# routed.net
KiCad netlist of a schematic drawn in Altium Designer
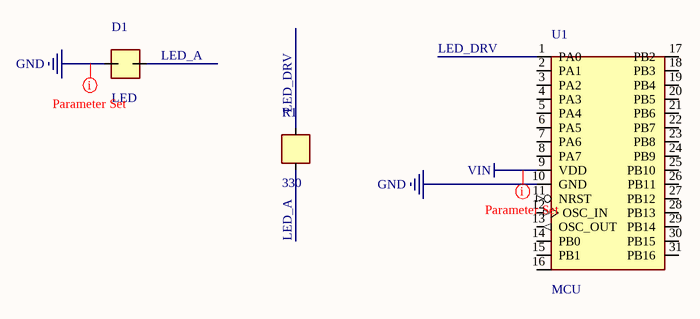
[diagram p0: routed.SchDoc]

(export (version "E")
  (design (tool "Eeschema 10.0.6"))
  (components
    (comp (ref "D1")
      (value "LED")
      (footprint "routed:Mini_LED_THT_3mm")
      (libsource (lib "routed") (part "Mini_LED"))
    )
    (comp (ref "R1")
      (value "330")
      (footprint "routed:Mini_R_0603")
      (libsource (lib "routed") (part "Mini_R"))
    )
    (comp (ref "U1")
      (value "MCU")
      (footprint "routed:Mini_QFP-32_7x7mm_P0.8mm")
      (libsource (lib "routed") (part "Mini_QFP32_IC"))
    )
  )
  (nets
    (net (code "1") (name "/LED_A") (class "Default")
      (node (ref "D1") (pin "2") (pinfunction "A_2") (pintype "passive"))
      (node (ref "R1") (pin "2") (pintype "passive"))
    )
    (net (code "2") (name "/LED_DRV") (class "Default")
      (node (ref "R1") (pin "1") (pintype "passive"))
      (node (ref "U1") (pin "1") (pinfunction "PA0_1") (pintype "bidirectional"))
    )
    (net (code "3") (name "GND") (class "Default")
      (node (ref "D1") (pin "1") (pinfunction "K_1") (pintype "passive"))
      (node (ref "U1") (pin "10") (pinfunction "GND_10") (pintype "power_in"))
    )
    (net (code "4") (name "VIN") (class "Default")
      (node (ref "U1") (pin "9") (pinfunction "VDD_9") (pintype "power_in"))
    )
    (net (code "5") (name "unconnected-(U1-EP-Pad32)") (class "Default")
      (node (ref "U1") (pin "32") (pinfunction "EP_32") (pintype "passive"))
    )
    (net (code "6") (name "unconnected-(U1-NRST-Pad11)") (class "Default")
      (node (ref "U1") (pin "11") (pinfunction "NRST_11") (pintype "input"))
    )
    (net (code "7") (name "unconnected-(U1-OSC_IN-Pad12)") (class "Default")
      (node (ref "U1") (pin "12") (pinfunction "OSC_IN_12") (pintype "input"))
    )
    (net (code "8") (name "unconnected-(U1-OSC_OUT-Pad13)") (class "Default")
      (node (ref "U1") (pin "13") (pinfunction "OSC_OUT_13") (pintype "output"))
    )
    (net (code "9") (name "unconnected-(U1-PA1-Pad2)") (class "Default")
      (node (ref "U1") (pin "2") (pinfunction "PA1_2") (pintype "bidirectional"))
    )
    (net (code "10") (name "unconnected-(U1-PA2-Pad3)") (class "Default")
      (node (ref "U1") (pin "3") (pinfunction "PA2_3") (pintype "bidirectional"))
    )
    (net (code "11") (name "unconnected-(U1-PA3-Pad4)") (class "Default")
      (node (ref "U1") (pin "4") (pinfunction "PA3_4") (pintype "bidirectional"))
    )
    (net (code "12") (name "unconnected-(U1-PA4-Pad5)") (class "Default")
      (node (ref "U1") (pin "5") (pinfunction "PA4_5") (pintype "bidirectional"))
    )
    (net (code "13") (name "unconnected-(U1-PA5-Pad6)") (class "Default")
      (node (ref "U1") (pin "6") (pinfunction "PA5_6") (pintype "bidirectional"))
    )
    (net (code "14") (name "unconnected-(U1-PA6-Pad7)") (class "Default")
      (node (ref "U1") (pin "7") (pinfunction "PA6_7") (pintype "bidirectional"))
    )
    (net (code "15") (name "unconnected-(U1-PA7-Pad8)") (class "Default")
      (node (ref "U1") (pin "8") (pinfunction "PA7_8") (pintype "bidirectional"))
    )
    (net (code "16") (name "unconnected-(U1-PB0-Pad14)") (class "Default")
      (node (ref "U1") (pin "14") (pinfunction "PB0_14") (pintype "bidirectional"))
    )
    (net (code "17") (name "unconnected-(U1-PB1-Pad15)") (class "Default")
      (node (ref "U1") (pin "15") (pinfunction "PB1_15") (pintype "tri_state"))
    )
    (net (code "18") (name "unconnected-(U1-PB2-Pad17)") (class "Default")
      (node (ref "U1") (pin "17") (pinfunction "PB2_17") (pintype "bidirectional"))
    )
    (net (code "19") (name "unconnected-(U1-PB3-Pad18)") (class "Default")
      (node (ref "U1") (pin "18") (pinfunction "PB3_18") (pintype "bidirectional"))
    )
    (net (code "20") (name "unconnected-(U1-PB4-Pad19)") (class "Default")
      (node (ref "U1") (pin "19") (pinfunction "PB4_19") (pintype "bidirectional"))
    )
    (net (code "21") (name "unconnected-(U1-PB5-Pad20)") (class "Default")
      (node (ref "U1") (pin "20") (pinfunction "PB5_20") (pintype "bidirectional"))
    )
    (net (code "22") (name "unconnected-(U1-PB6-Pad21)") (class "Default")
      (node (ref "U1") (pin "21") (pinfunction "PB6_21") (pintype "bidirectional"))
    )
    (net (code "23") (name "unconnected-(U1-PB7-Pad22)") (class "Default")
      (node (ref "U1") (pin "22") (pinfunction "PB7_22") (pintype "bidirectional"))
    )
    (net (code "24") (name "unconnected-(U1-PB8-Pad23)") (class "Default")
      (node (ref "U1") (pin "23") (pinfunction "PB8_23") (pintype "bidirectional"))
    )
    (net (code "25") (name "unconnected-(U1-PB9-Pad24)") (class "Default")
      (node (ref "U1") (pin "24") (pinfunction "PB9_24") (pintype "bidirectional"))
    )
    (net (code "26") (name "unconnected-(U1-PB10-Pad25)") (class "Default")
      (node (ref "U1") (pin "25") (pinfunction "PB10_25") (pintype "bidirectional"))
    )
    (net (code "27") (name "unconnected-(U1-PB11-Pad26)") (class "Default")
      (node (ref "U1") (pin "26") (pinfunction "PB11_26") (pintype "bidirectional"))
    )
    (net (code "28") (name "unconnected-(U1-PB12-Pad27)") (class "Default")
      (node (ref "U1") (pin "27") (pinfunction "PB12_27") (pintype "bidirectional"))
    )
    (net (code "29") (name "unconnected-(U1-PB13-Pad28)") (class "Default")
      (node (ref "U1") (pin "28") (pinfunction "PB13_28") (pintype "bidirectional"))
    )
    (net (code "30") (name "unconnected-(U1-PB14-Pad29)") (class "Default")
      (node (ref "U1") (pin "29") (pinfunction "PB14_29") (pintype "bidirectional"))
    )
    (net (code "31") (name "unconnected-(U1-PB15-Pad30)") (class "Default")
      (node (ref "U1") (pin "30") (pinfunction "PB15_30") (pintype "bidirectional"))
    )
    (net (code "32") (name "unconnected-(U1-PB16-Pad31)") (class "Default")
      (node (ref "U1") (pin "31") (pinfunction "PB16_31") (pintype "bidirectional"))
    )
    (net (code "33") (name "unconnected-(U1-Pad16)") (class "Default")
      (node (ref "U1") (pin "16") (pintype "passive"))
    )
  )
)
